# rgb-daughter.net
KiCad netlist of a schematic drawn in EAGLE
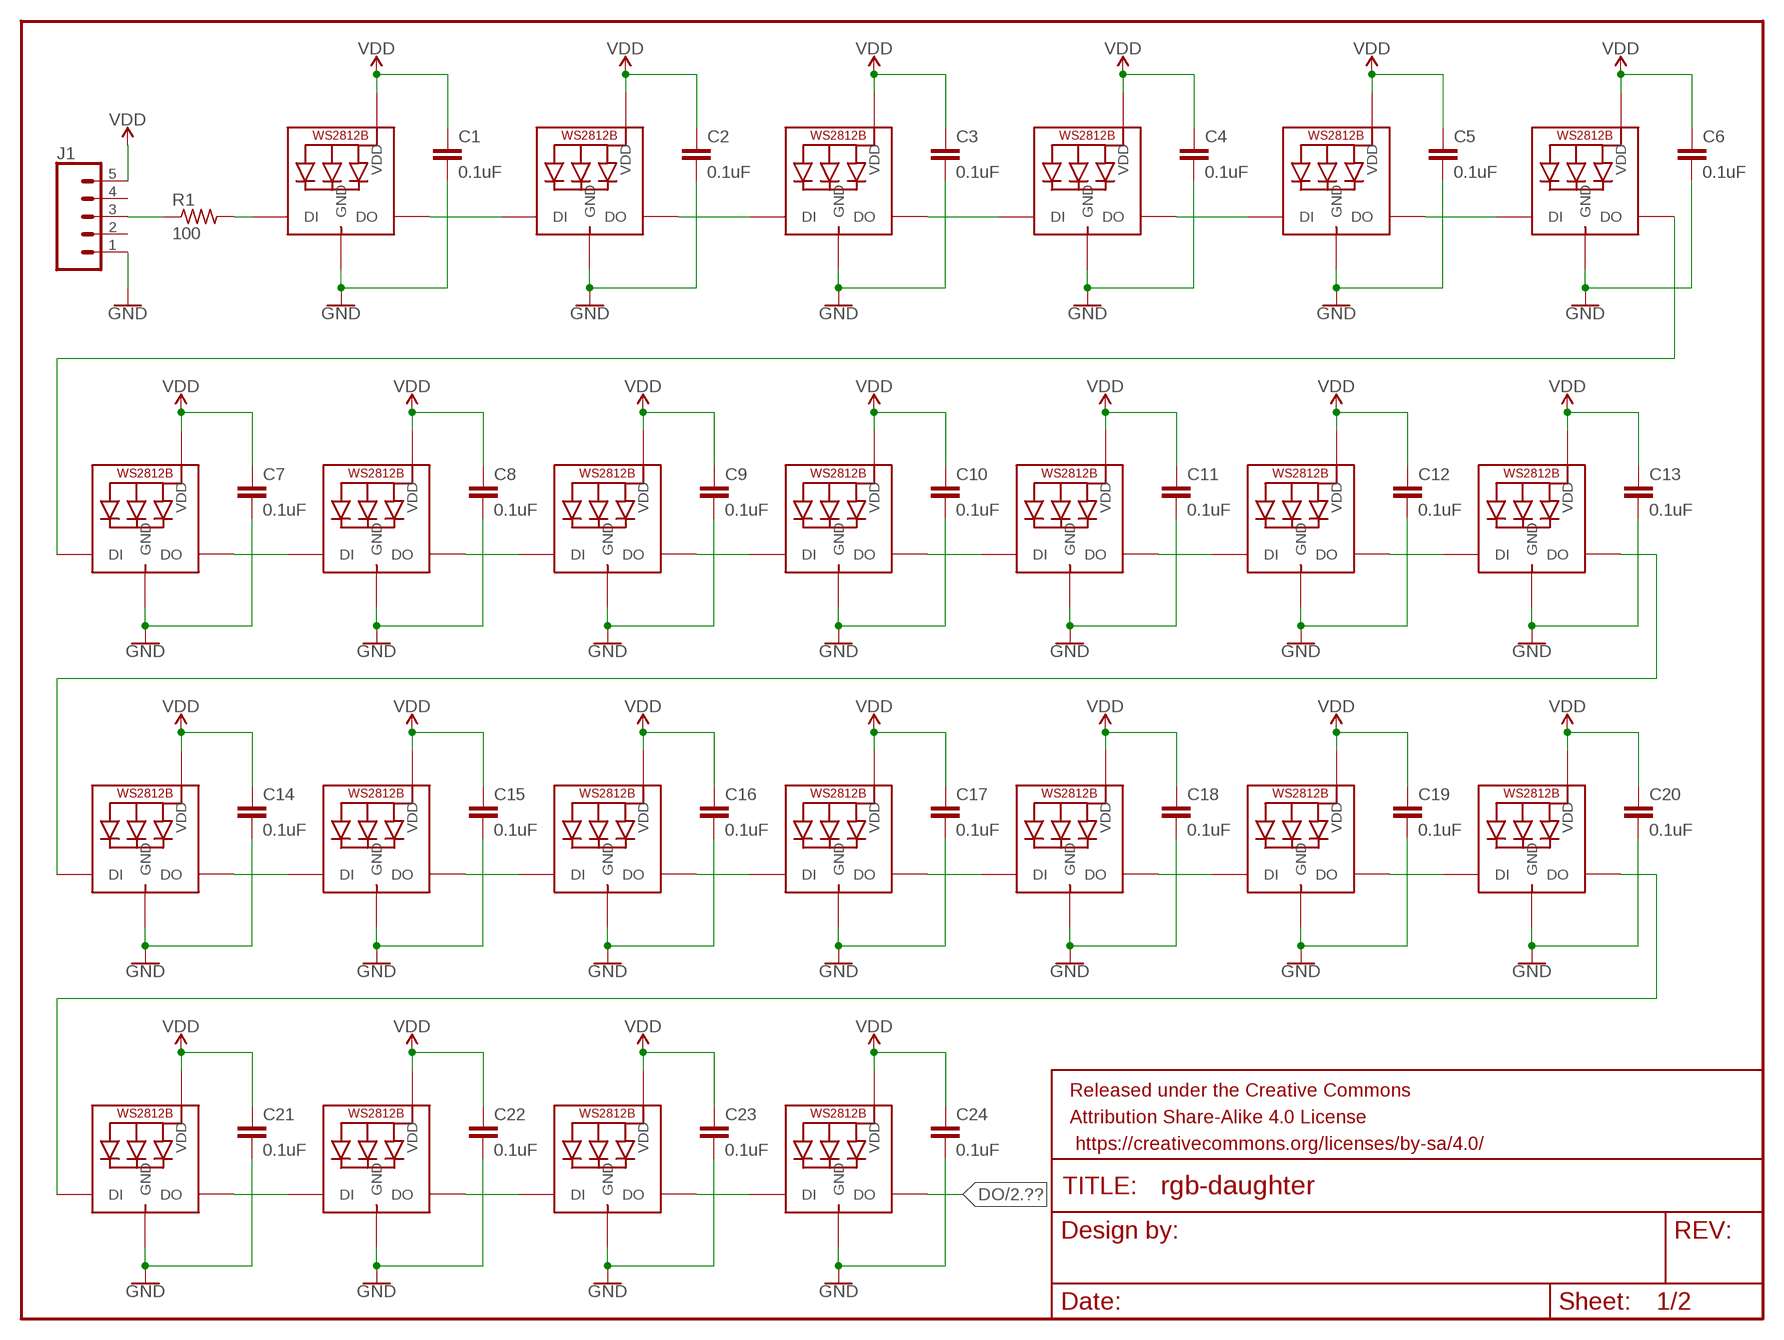
[diagram p0: schematic, sheet 1]
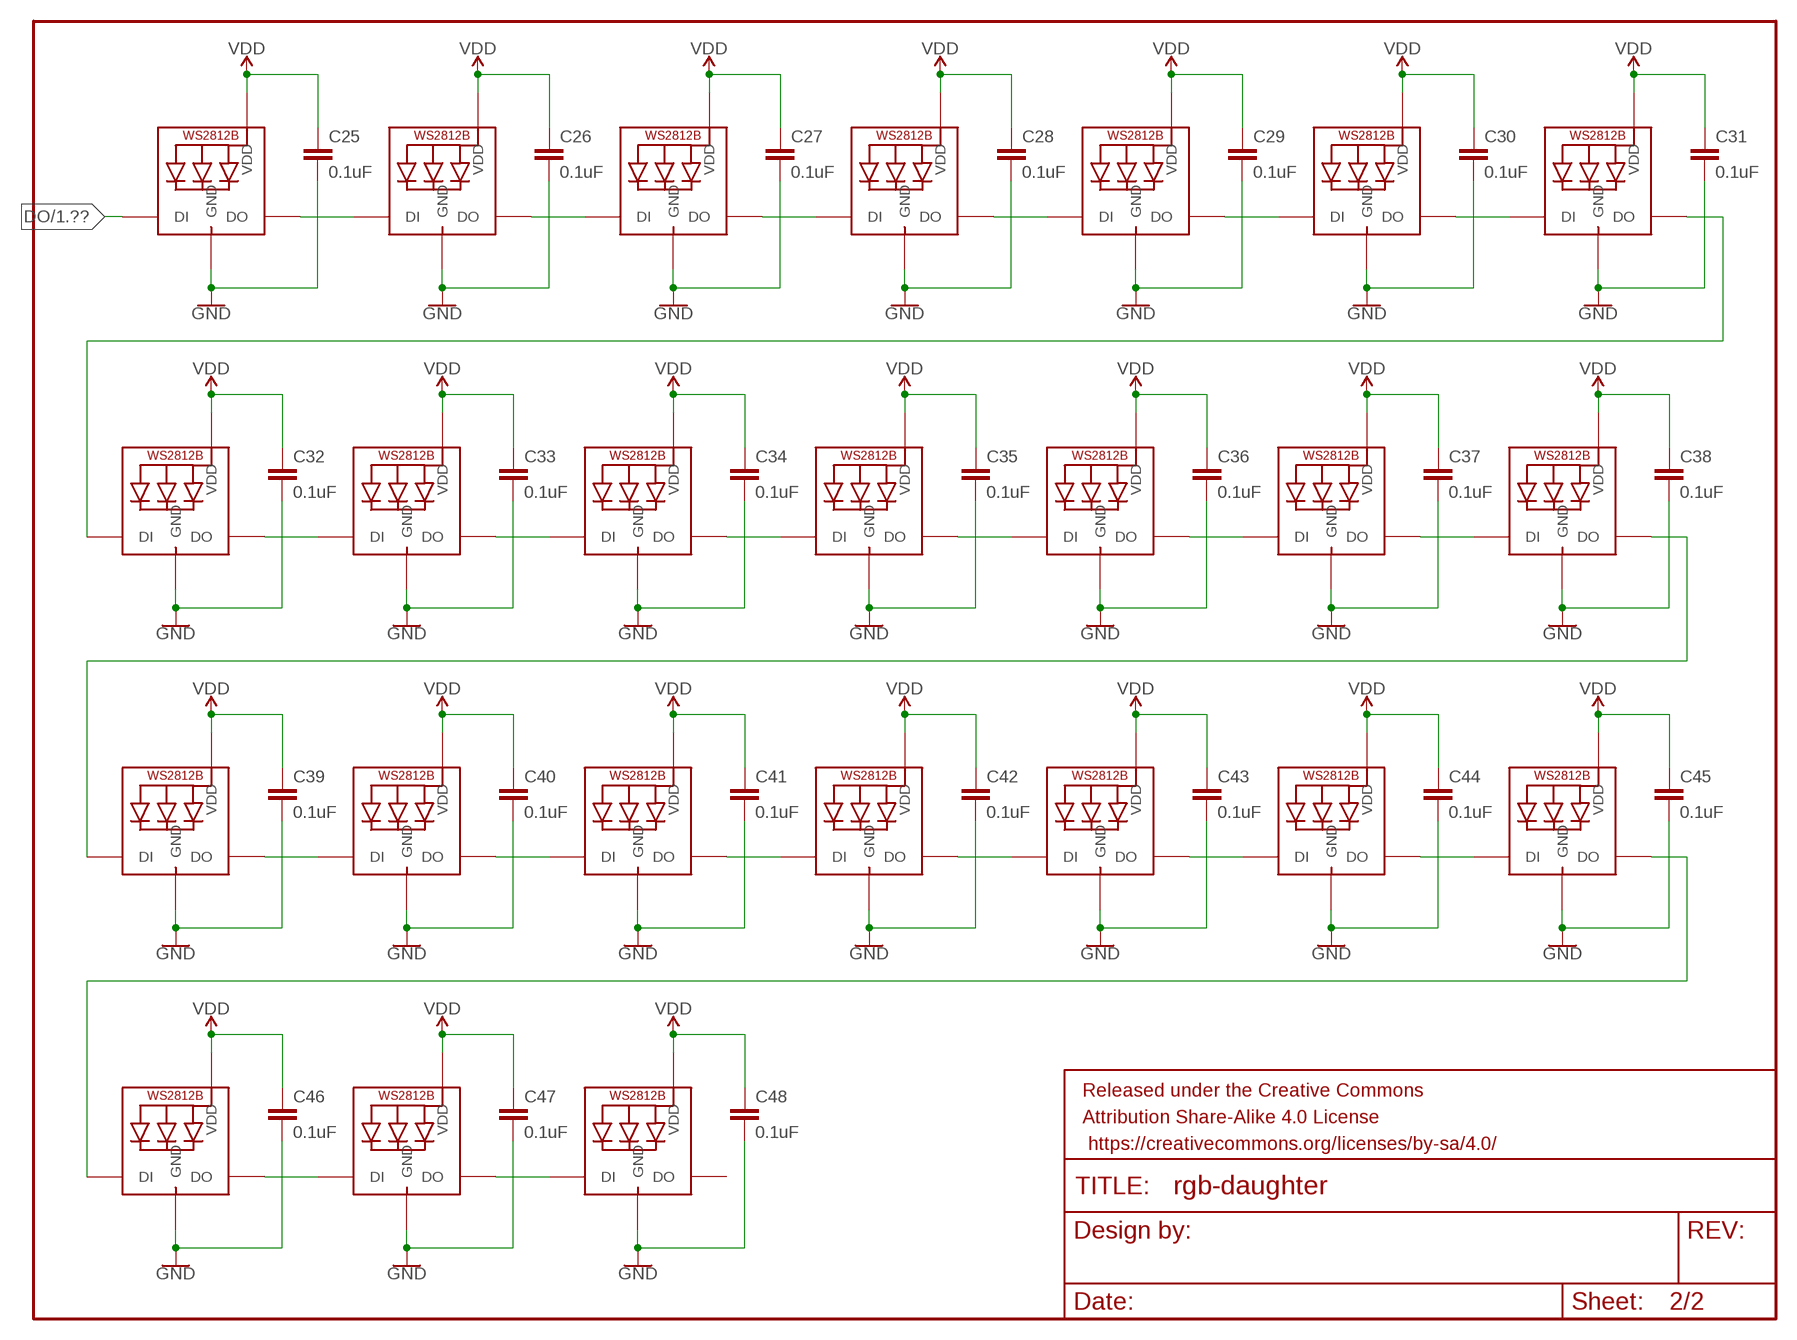
[diagram p1: schematic, sheet 2]

(export (version "E")
  (design (tool "Eeschema 10.0.6"))
  (components
    (comp (ref "C1")
      (value "0.1uF")
      (footprint "eagle-import:0603")
      (libsource (lib "eagle-import") (part "0.1UF-0603-25V-(+80/-20%)"))
    )
    (comp (ref "C2")
      (value "0.1uF")
      (footprint "eagle-import:0603")
      (libsource (lib "eagle-import") (part "0.1UF-0603-25V-(+80/-20%)"))
    )
    (comp (ref "C3")
      (value "0.1uF")
      (footprint "eagle-import:0603")
      (libsource (lib "eagle-import") (part "0.1UF-0603-25V-(+80/-20%)"))
    )
    (comp (ref "C4")
      (value "0.1uF")
      (footprint "eagle-import:0603")
      (libsource (lib "eagle-import") (part "0.1UF-0603-25V-(+80/-20%)"))
    )
    (comp (ref "C5")
      (value "0.1uF")
      (footprint "eagle-import:0603")
      (libsource (lib "eagle-import") (part "0.1UF-0603-25V-(+80/-20%)"))
    )
    (comp (ref "C6")
      (value "0.1uF")
      (footprint "eagle-import:0603")
      (libsource (lib "eagle-import") (part "0.1UF-0603-25V-(+80/-20%)"))
    )
    (comp (ref "C7")
      (value "0.1uF")
      (footprint "eagle-import:0603")
      (libsource (lib "eagle-import") (part "0.1UF-0603-25V-(+80/-20%)"))
    )
    (comp (ref "C8")
      (value "0.1uF")
      (footprint "eagle-import:0603")
      (libsource (lib "eagle-import") (part "0.1UF-0603-25V-(+80/-20%)"))
    )
    (comp (ref "C9")
      (value "0.1uF")
      (footprint "eagle-import:0603")
      (libsource (lib "eagle-import") (part "0.1UF-0603-25V-(+80/-20%)"))
    )
    (comp (ref "C10")
      (value "0.1uF")
      (footprint "eagle-import:0603")
      (libsource (lib "eagle-import") (part "0.1UF-0603-25V-(+80/-20%)"))
    )
    (comp (ref "C11")
      (value "0.1uF")
      (footprint "eagle-import:0603")
      (libsource (lib "eagle-import") (part "0.1UF-0603-25V-(+80/-20%)"))
    )
    (comp (ref "C12")
      (value "0.1uF")
      (footprint "eagle-import:0603")
      (libsource (lib "eagle-import") (part "0.1UF-0603-25V-(+80/-20%)"))
    )
    (comp (ref "C13")
      (value "0.1uF")
      (footprint "eagle-import:0603")
      (libsource (lib "eagle-import") (part "0.1UF-0603-25V-(+80/-20%)"))
    )
    (comp (ref "C14")
      (value "0.1uF")
      (footprint "eagle-import:0603")
      (libsource (lib "eagle-import") (part "0.1UF-0603-25V-(+80/-20%)"))
    )
    (comp (ref "C15")
      (value "0.1uF")
      (footprint "eagle-import:0603")
      (libsource (lib "eagle-import") (part "0.1UF-0603-25V-(+80/-20%)"))
    )
    (comp (ref "C16")
      (value "0.1uF")
      (footprint "eagle-import:0603")
      (libsource (lib "eagle-import") (part "0.1UF-0603-25V-(+80/-20%)"))
    )
    (comp (ref "C17")
      (value "0.1uF")
      (footprint "eagle-import:0603")
      (libsource (lib "eagle-import") (part "0.1UF-0603-25V-(+80/-20%)"))
    )
    (comp (ref "C18")
      (value "0.1uF")
      (footprint "eagle-import:0603")
      (libsource (lib "eagle-import") (part "0.1UF-0603-25V-(+80/-20%)"))
    )
    (comp (ref "C19")
      (value "0.1uF")
      (footprint "eagle-import:0603")
      (libsource (lib "eagle-import") (part "0.1UF-0603-25V-(+80/-20%)"))
    )
    (comp (ref "C20")
      (value "0.1uF")
      (footprint "eagle-import:0603")
      (libsource (lib "eagle-import") (part "0.1UF-0603-25V-(+80/-20%)"))
    )
    (comp (ref "C21")
      (value "0.1uF")
      (footprint "eagle-import:0603")
      (libsource (lib "eagle-import") (part "0.1UF-0603-25V-(+80/-20%)"))
    )
    (comp (ref "C22")
      (value "0.1uF")
      (footprint "eagle-import:0603")
      (libsource (lib "eagle-import") (part "0.1UF-0603-25V-(+80/-20%)"))
    )
    (comp (ref "C23")
      (value "0.1uF")
      (footprint "eagle-import:0603")
      (libsource (lib "eagle-import") (part "0.1UF-0603-25V-(+80/-20%)"))
    )
    (comp (ref "C24")
      (value "0.1uF")
      (footprint "eagle-import:0603")
      (libsource (lib "eagle-import") (part "0.1UF-0603-25V-(+80/-20%)"))
    )
    (comp (ref "FRAME1")
      (value "FRAME-LETTER")
      (footprint "eagle-import:CREATIVE_COMMONS")
      (libsource (lib "eagle-import") (part "FRAME-LETTER"))
    )
    (comp (ref "J1")
      (value "CONN_051.27MM")
      (footprint "eagle-import:1X05_1.27MM")
      (libsource (lib "eagle-import") (part "CONN_051.27MM"))
    )
    (comp (ref "LED1")
      (value "WS2812B3535")
      (footprint "eagle-import:LED3535")
      (libsource (lib "eagle-import") (part "WS2812B3535"))
    )
    (comp (ref "LED2")
      (value "WS2812B3535")
      (footprint "eagle-import:LED3535")
      (libsource (lib "eagle-import") (part "WS2812B3535"))
    )
    (comp (ref "LED3")
      (value "WS2812B3535")
      (footprint "eagle-import:LED3535")
      (libsource (lib "eagle-import") (part "WS2812B3535"))
    )
    (comp (ref "LED4")
      (value "WS2812B3535")
      (footprint "eagle-import:LED3535")
      (libsource (lib "eagle-import") (part "WS2812B3535"))
    )
    (comp (ref "LED5")
      (value "WS2812B3535")
      (footprint "eagle-import:LED3535")
      (libsource (lib "eagle-import") (part "WS2812B3535"))
    )
    (comp (ref "LED6")
      (value "WS2812B3535")
      (footprint "eagle-import:LED3535")
      (libsource (lib "eagle-import") (part "WS2812B3535"))
    )
    (comp (ref "LED7")
      (value "WS2812B3535")
      (footprint "eagle-import:LED3535")
      (libsource (lib "eagle-import") (part "WS2812B3535"))
    )
    (comp (ref "LED8")
      (value "WS2812B3535")
      (footprint "eagle-import:LED3535")
      (libsource (lib "eagle-import") (part "WS2812B3535"))
    )
    (comp (ref "LED9")
      (value "WS2812B3535")
      (footprint "eagle-import:LED3535")
      (libsource (lib "eagle-import") (part "WS2812B3535"))
    )
    (comp (ref "LED10")
      (value "WS2812B3535")
      (footprint "eagle-import:LED3535")
      (libsource (lib "eagle-import") (part "WS2812B3535"))
    )
    (comp (ref "LED11")
      (value "WS2812B3535")
      (footprint "eagle-import:LED3535")
      (libsource (lib "eagle-import") (part "WS2812B3535"))
    )
    (comp (ref "LED12")
      (value "WS2812B3535")
      (footprint "eagle-import:LED3535")
      (libsource (lib "eagle-import") (part "WS2812B3535"))
    )
    (comp (ref "LED13")
      (value "WS2812B3535")
      (footprint "eagle-import:LED3535")
      (libsource (lib "eagle-import") (part "WS2812B3535"))
    )
    (comp (ref "LED14")
      (value "WS2812B3535")
      (footprint "eagle-import:LED3535")
      (libsource (lib "eagle-import") (part "WS2812B3535"))
    )
    (comp (ref "LED15")
      (value "WS2812B3535")
      (footprint "eagle-import:LED3535")
      (libsource (lib "eagle-import") (part "WS2812B3535"))
    )
    (comp (ref "LED16")
      (value "WS2812B3535")
      (footprint "eagle-import:LED3535")
      (libsource (lib "eagle-import") (part "WS2812B3535"))
    )
    (comp (ref "LED17")
      (value "WS2812B3535")
      (footprint "eagle-import:LED3535")
      (libsource (lib "eagle-import") (part "WS2812B3535"))
    )
    (comp (ref "LED18")
      (value "WS2812B3535")
      (footprint "eagle-import:LED3535")
      (libsource (lib "eagle-import") (part "WS2812B3535"))
    )
    (comp (ref "LED19")
      (value "WS2812B3535")
      (footprint "eagle-import:LED3535")
      (libsource (lib "eagle-import") (part "WS2812B3535"))
    )
    (comp (ref "LED20")
      (value "WS2812B3535")
      (footprint "eagle-import:LED3535")
      (libsource (lib "eagle-import") (part "WS2812B3535"))
    )
    (comp (ref "LED21")
      (value "WS2812B3535")
      (footprint "eagle-import:LED3535")
      (libsource (lib "eagle-import") (part "WS2812B3535"))
    )
    (comp (ref "LED22")
      (value "WS2812B3535")
      (footprint "eagle-import:LED3535")
      (libsource (lib "eagle-import") (part "WS2812B3535"))
    )
    (comp (ref "LED23")
      (value "WS2812B3535")
      (footprint "eagle-import:LED3535")
      (libsource (lib "eagle-import") (part "WS2812B3535"))
    )
    (comp (ref "LED48")
      (value "WS2812B3535")
      (footprint "eagle-import:LED3535")
      (libsource (lib "eagle-import") (part "WS2812B3535"))
    )
    (comp (ref "R1")
      (value "100")
      (footprint "eagle-import:M0805")
      (libsource (lib "eagle-import") (part "R-US_M0805"))
    )
    (comp (ref "C25")
      (value "0.1uF")
      (footprint "eagle-import:0603")
      (libsource (lib "eagle-import") (part "0.1UF-0603-25V-(+80/-20%)"))
    )
    (comp (ref "C26")
      (value "0.1uF")
      (footprint "eagle-import:0603")
      (libsource (lib "eagle-import") (part "0.1UF-0603-25V-(+80/-20%)"))
    )
    (comp (ref "C27")
      (value "0.1uF")
      (footprint "eagle-import:0603")
      (libsource (lib "eagle-import") (part "0.1UF-0603-25V-(+80/-20%)"))
    )
    (comp (ref "C28")
      (value "0.1uF")
      (footprint "eagle-import:0603")
      (libsource (lib "eagle-import") (part "0.1UF-0603-25V-(+80/-20%)"))
    )
    (comp (ref "C29")
      (value "0.1uF")
      (footprint "eagle-import:0603")
      (libsource (lib "eagle-import") (part "0.1UF-0603-25V-(+80/-20%)"))
    )
    (comp (ref "C30")
      (value "0.1uF")
      (footprint "eagle-import:0603")
      (libsource (lib "eagle-import") (part "0.1UF-0603-25V-(+80/-20%)"))
    )
    (comp (ref "C31")
      (value "0.1uF")
      (footprint "eagle-import:0603")
      (libsource (lib "eagle-import") (part "0.1UF-0603-25V-(+80/-20%)"))
    )
    (comp (ref "C32")
      (value "0.1uF")
      (footprint "eagle-import:0603")
      (libsource (lib "eagle-import") (part "0.1UF-0603-25V-(+80/-20%)"))
    )
    (comp (ref "C33")
      (value "0.1uF")
      (footprint "eagle-import:0603")
      (libsource (lib "eagle-import") (part "0.1UF-0603-25V-(+80/-20%)"))
    )
    (comp (ref "C34")
      (value "0.1uF")
      (footprint "eagle-import:0603")
      (libsource (lib "eagle-import") (part "0.1UF-0603-25V-(+80/-20%)"))
    )
    (comp (ref "C35")
      (value "0.1uF")
      (footprint "eagle-import:0603")
      (libsource (lib "eagle-import") (part "0.1UF-0603-25V-(+80/-20%)"))
    )
    (comp (ref "C36")
      (value "0.1uF")
      (footprint "eagle-import:0603")
      (libsource (lib "eagle-import") (part "0.1UF-0603-25V-(+80/-20%)"))
    )
    (comp (ref "C37")
      (value "0.1uF")
      (footprint "eagle-import:0603")
      (libsource (lib "eagle-import") (part "0.1UF-0603-25V-(+80/-20%)"))
    )
    (comp (ref "C38")
      (value "0.1uF")
      (footprint "eagle-import:0603")
      (libsource (lib "eagle-import") (part "0.1UF-0603-25V-(+80/-20%)"))
    )
    (comp (ref "C39")
      (value "0.1uF")
      (footprint "eagle-import:0603")
      (libsource (lib "eagle-import") (part "0.1UF-0603-25V-(+80/-20%)"))
    )
    (comp (ref "C40")
      (value "0.1uF")
      (footprint "eagle-import:0603")
      (libsource (lib "eagle-import") (part "0.1UF-0603-25V-(+80/-20%)"))
    )
    (comp (ref "C41")
      (value "0.1uF")
      (footprint "eagle-import:0603")
      (libsource (lib "eagle-import") (part "0.1UF-0603-25V-(+80/-20%)"))
    )
    (comp (ref "C42")
      (value "0.1uF")
      (footprint "eagle-import:0603")
      (libsource (lib "eagle-import") (part "0.1UF-0603-25V-(+80/-20%)"))
    )
    (comp (ref "C43")
      (value "0.1uF")
      (footprint "eagle-import:0603")
      (libsource (lib "eagle-import") (part "0.1UF-0603-25V-(+80/-20%)"))
    )
    (comp (ref "C44")
      (value "0.1uF")
      (footprint "eagle-import:0603")
      (libsource (lib "eagle-import") (part "0.1UF-0603-25V-(+80/-20%)"))
    )
    (comp (ref "C45")
      (value "0.1uF")
      (footprint "eagle-import:0603")
      (libsource (lib "eagle-import") (part "0.1UF-0603-25V-(+80/-20%)"))
    )
    (comp (ref "C46")
      (value "0.1uF")
      (footprint "eagle-import:0603")
      (libsource (lib "eagle-import") (part "0.1UF-0603-25V-(+80/-20%)"))
    )
    (comp (ref "C47")
      (value "0.1uF")
      (footprint "eagle-import:0603")
      (libsource (lib "eagle-import") (part "0.1UF-0603-25V-(+80/-20%)"))
    )
    (comp (ref "C48")
      (value "0.1uF")
      (footprint "eagle-import:0603")
      (libsource (lib "eagle-import") (part "0.1UF-0603-25V-(+80/-20%)"))
    )
    (comp (ref "FRAME2")
      (value "FRAME-LETTER")
      (footprint "eagle-import:CREATIVE_COMMONS")
      (libsource (lib "eagle-import") (part "FRAME-LETTER"))
    )
    (comp (ref "LED24")
      (value "WS2812B3535")
      (footprint "eagle-import:LED3535")
      (libsource (lib "eagle-import") (part "WS2812B3535"))
    )
    (comp (ref "LED25")
      (value "WS2812B3535")
      (footprint "eagle-import:LED3535")
      (libsource (lib "eagle-import") (part "WS2812B3535"))
    )
    (comp (ref "LED26")
      (value "WS2812B3535")
      (footprint "eagle-import:LED3535")
      (libsource (lib "eagle-import") (part "WS2812B3535"))
    )
    (comp (ref "LED27")
      (value "WS2812B3535")
      (footprint "eagle-import:LED3535")
      (libsource (lib "eagle-import") (part "WS2812B3535"))
    )
    (comp (ref "LED28")
      (value "WS2812B3535")
      (footprint "eagle-import:LED3535")
      (libsource (lib "eagle-import") (part "WS2812B3535"))
    )
    (comp (ref "LED29")
      (value "WS2812B3535")
      (footprint "eagle-import:LED3535")
      (libsource (lib "eagle-import") (part "WS2812B3535"))
    )
    (comp (ref "LED30")
      (value "WS2812B3535")
      (footprint "eagle-import:LED3535")
      (libsource (lib "eagle-import") (part "WS2812B3535"))
    )
    (comp (ref "LED31")
      (value "WS2812B3535")
      (footprint "eagle-import:LED3535")
      (libsource (lib "eagle-import") (part "WS2812B3535"))
    )
    (comp (ref "LED32")
      (value "WS2812B3535")
      (footprint "eagle-import:LED3535")
      (libsource (lib "eagle-import") (part "WS2812B3535"))
    )
    (comp (ref "LED33")
      (value "WS2812B3535")
      (footprint "eagle-import:LED3535")
      (libsource (lib "eagle-import") (part "WS2812B3535"))
    )
    (comp (ref "LED34")
      (value "WS2812B3535")
      (footprint "eagle-import:LED3535")
      (libsource (lib "eagle-import") (part "WS2812B3535"))
    )
    (comp (ref "LED35")
      (value "WS2812B3535")
      (footprint "eagle-import:LED3535")
      (libsource (lib "eagle-import") (part "WS2812B3535"))
    )
    (comp (ref "LED36")
      (value "WS2812B3535")
      (footprint "eagle-import:LED3535")
      (libsource (lib "eagle-import") (part "WS2812B3535"))
    )
    (comp (ref "LED37")
      (value "WS2812B3535")
      (footprint "eagle-import:LED3535")
      (libsource (lib "eagle-import") (part "WS2812B3535"))
    )
    (comp (ref "LED38")
      (value "WS2812B3535")
      (footprint "eagle-import:LED3535")
      (libsource (lib "eagle-import") (part "WS2812B3535"))
    )
    (comp (ref "LED39")
      (value "WS2812B3535")
      (footprint "eagle-import:LED3535")
      (libsource (lib "eagle-import") (part "WS2812B3535"))
    )
    (comp (ref "LED40")
      (value "WS2812B3535")
      (footprint "eagle-import:LED3535")
      (libsource (lib "eagle-import") (part "WS2812B3535"))
    )
    (comp (ref "LED41")
      (value "WS2812B3535")
      (footprint "eagle-import:LED3535")
      (libsource (lib "eagle-import") (part "WS2812B3535"))
    )
    (comp (ref "LED42")
      (value "WS2812B3535")
      (footprint "eagle-import:LED3535")
      (libsource (lib "eagle-import") (part "WS2812B3535"))
    )
    (comp (ref "LED43")
      (value "WS2812B3535")
      (footprint "eagle-import:LED3535")
      (libsource (lib "eagle-import") (part "WS2812B3535"))
    )
    (comp (ref "LED44")
      (value "WS2812B3535")
      (footprint "eagle-import:LED3535")
      (libsource (lib "eagle-import") (part "WS2812B3535"))
    )
    (comp (ref "LED45")
      (value "WS2812B3535")
      (footprint "eagle-import:LED3535")
      (libsource (lib "eagle-import") (part "WS2812B3535"))
    )
    (comp (ref "LED46")
      (value "WS2812B3535")
      (footprint "eagle-import:LED3535")
      (libsource (lib "eagle-import") (part "WS2812B3535"))
    )
    (comp (ref "LED47")
      (value "WS2812B3535")
      (footprint "eagle-import:LED3535")
      (libsource (lib "eagle-import") (part "WS2812B3535"))
    )
  )
  (nets
    (net (code "1") (name "DO") (class "Default")
      (node (ref "LED24") (pin "1") (pinfunction "DI_1") (pintype "input"))
      (node (ref "LED48") (pin "3") (pinfunction "DO_3") (pintype "output"))
    )
    (net (code "2") (name "GND") (class "Default")
      (node (ref "C1") (pin "2") (pinfunction "2_2") (pintype "passive"))
      (node (ref "C10") (pin "2") (pinfunction "2_2") (pintype "passive"))
      (node (ref "C11") (pin "2") (pinfunction "2_2") (pintype "passive"))
      (node (ref "C12") (pin "2") (pinfunction "2_2") (pintype "passive"))
      (node (ref "C13") (pin "2") (pinfunction "2_2") (pintype "passive"))
      (node (ref "C14") (pin "2") (pinfunction "2_2") (pintype "passive"))
      (node (ref "C15") (pin "2") (pinfunction "2_2") (pintype "passive"))
      (node (ref "C16") (pin "2") (pinfunction "2_2") (pintype "passive"))
      (node (ref "C17") (pin "2") (pinfunction "2_2") (pintype "passive"))
      (node (ref "C18") (pin "2") (pinfunction "2_2") (pintype "passive"))
      (node (ref "C19") (pin "2") (pinfunction "2_2") (pintype "passive"))
      (node (ref "C2") (pin "2") (pinfunction "2_2") (pintype "passive"))
      (node (ref "C20") (pin "2") (pinfunction "2_2") (pintype "passive"))
      (node (ref "C21") (pin "2") (pinfunction "2_2") (pintype "passive"))
      (node (ref "C22") (pin "2") (pinfunction "2_2") (pintype "passive"))
      (node (ref "C23") (pin "2") (pinfunction "2_2") (pintype "passive"))
      (node (ref "C24") (pin "2") (pinfunction "2_2") (pintype "passive"))
      (node (ref "C25") (pin "2") (pinfunction "2_2") (pintype "passive"))
      (node (ref "C26") (pin "2") (pinfunction "2_2") (pintype "passive"))
      (node (ref "C27") (pin "2") (pinfunction "2_2") (pintype "passive"))
      (node (ref "C28") (pin "2") (pinfunction "2_2") (pintype "passive"))
      (node (ref "C29") (pin "2") (pinfunction "2_2") (pintype "passive"))
      (node (ref "C3") (pin "2") (pinfunction "2_2") (pintype "passive"))
      (node (ref "C30") (pin "2") (pinfunction "2_2") (pintype "passive"))
      (node (ref "C31") (pin "2") (pinfunction "2_2") (pintype "passive"))
      (node (ref "C32") (pin "2") (pinfunction "2_2") (pintype "passive"))
      (node (ref "C33") (pin "2") (pinfunction "2_2") (pintype "passive"))
      (node (ref "C34") (pin "2") (pinfunction "2_2") (pintype "passive"))
      (node (ref "C35") (pin "2") (pinfunction "2_2") (pintype "passive"))
      (node (ref "C36") (pin "2") (pinfunction "2_2") (pintype "passive"))
      (node (ref "C37") (pin "2") (pinfunction "2_2") (pintype "passive"))
      (node (ref "C38") (pin "2") (pinfunction "2_2") (pintype "passive"))
      (node (ref "C39") (pin "2") (pinfunction "2_2") (pintype "passive"))
      (node (ref "C4") (pin "2") (pinfunction "2_2") (pintype "passive"))
      (node (ref "C40") (pin "2") (pinfunction "2_2") (pintype "passive"))
      (node (ref "C41") (pin "2") (pinfunction "2_2") (pintype "passive"))
      (node (ref "C42") (pin "2") (pinfunction "2_2") (pintype "passive"))
      (node (ref "C43") (pin "2") (pinfunction "2_2") (pintype "passive"))
      (node (ref "C44") (pin "2") (pinfunction "2_2") (pintype "passive"))
      (node (ref "C45") (pin "2") (pinfunction "2_2") (pintype "passive"))
      (node (ref "C46") (pin "2") (pinfunction "2_2") (pintype "passive"))
      (node (ref "C47") (pin "2") (pinfunction "2_2") (pintype "passive"))
      (node (ref "C48") (pin "2") (pinfunction "2_2") (pintype "passive"))
      (node (ref "C5") (pin "2") (pinfunction "2_2") (pintype "passive"))
      (node (ref "C6") (pin "2") (pinfunction "2_2") (pintype "passive"))
      (node (ref "C7") (pin "2") (pinfunction "2_2") (pintype "passive"))
      (node (ref "C8") (pin "2") (pinfunction "2_2") (pintype "passive"))
      (node (ref "C9") (pin "2") (pinfunction "2_2") (pintype "passive"))
      (node (ref "J1") (pin "1") (pinfunction "1_1") (pintype "passive"))
      (node (ref "LED1") (pin "4") (pinfunction "GND_4") (pintype "power_in"))
      (node (ref "LED10") (pin "4") (pinfunction "GND_4") (pintype "power_in"))
      (node (ref "LED11") (pin "4") (pinfunction "GND_4") (pintype "power_in"))
      (node (ref "LED12") (pin "4") (pinfunction "GND_4") (pintype "power_in"))
      (node (ref "LED13") (pin "4") (pinfunction "GND_4") (pintype "power_in"))
      (node (ref "LED14") (pin "4") (pinfunction "GND_4") (pintype "power_in"))
      (node (ref "LED15") (pin "4") (pinfunction "GND_4") (pintype "power_in"))
      (node (ref "LED16") (pin "4") (pinfunction "GND_4") (pintype "power_in"))
      (node (ref "LED17") (pin "4") (pinfunction "GND_4") (pintype "power_in"))
      (node (ref "LED18") (pin "4") (pinfunction "GND_4") (pintype "power_in"))
      (node (ref "LED19") (pin "4") (pinfunction "GND_4") (pintype "power_in"))
      (node (ref "LED2") (pin "4") (pinfunction "GND_4") (pintype "power_in"))
      (node (ref "LED20") (pin "4") (pinfunction "GND_4") (pintype "power_in"))
      (node (ref "LED21") (pin "4") (pinfunction "GND_4") (pintype "power_in"))
      (node (ref "LED22") (pin "4") (pinfunction "GND_4") (pintype "power_in"))
      (node (ref "LED23") (pin "4") (pinfunction "GND_4") (pintype "power_in"))
      (node (ref "LED24") (pin "4") (pinfunction "GND_4") (pintype "power_in"))
      (node (ref "LED25") (pin "4") (pinfunction "GND_4") (pintype "power_in"))
      (node (ref "LED26") (pin "4") (pinfunction "GND_4") (pintype "power_in"))
      (node (ref "LED27") (pin "4") (pinfunction "GND_4") (pintype "power_in"))
      (node (ref "LED28") (pin "4") (pinfunction "GND_4") (pintype "power_in"))
      (node (ref "LED29") (pin "4") (pinfunction "GND_4") (pintype "power_in"))
      (node (ref "LED3") (pin "4") (pinfunction "GND_4") (pintype "power_in"))
      (node (ref "LED30") (pin "4") (pinfunction "GND_4") (pintype "power_in"))
      (node (ref "LED31") (pin "4") (pinfunction "GND_4") (pintype "power_in"))
      (node (ref "LED32") (pin "4") (pinfunction "GND_4") (pintype "power_in"))
      (node (ref "LED33") (pin "4") (pinfunction "GND_4") (pintype "power_in"))
      (node (ref "LED34") (pin "4") (pinfunction "GND_4") (pintype "power_in"))
      (node (ref "LED35") (pin "4") (pinfunction "GND_4") (pintype "power_in"))
      (node (ref "LED36") (pin "4") (pinfunction "GND_4") (pintype "power_in"))
      (node (ref "LED37") (pin "4") (pinfunction "GND_4") (pintype "power_in"))
      (node (ref "LED38") (pin "4") (pinfunction "GND_4") (pintype "power_in"))
      (node (ref "LED39") (pin "4") (pinfunction "GND_4") (pintype "power_in"))
      (node (ref "LED4") (pin "4") (pinfunction "GND_4") (pintype "power_in"))
      (node (ref "LED40") (pin "4") (pinfunction "GND_4") (pintype "power_in"))
      (node (ref "LED41") (pin "4") (pinfunction "GND_4") (pintype "power_in"))
      (node (ref "LED42") (pin "4") (pinfunction "GND_4") (pintype "power_in"))
      (node (ref "LED43") (pin "4") (pinfunction "GND_4") (pintype "power_in"))
      (node (ref "LED44") (pin "4") (pinfunction "GND_4") (pintype "power_in"))
      (node (ref "LED45") (pin "4") (pinfunction "GND_4") (pintype "power_in"))
      (node (ref "LED46") (pin "4") (pinfunction "GND_4") (pintype "power_in"))
      (node (ref "LED47") (pin "4") (pinfunction "GND_4") (pintype "power_in"))
      (node (ref "LED48") (pin "4") (pinfunction "GND_4") (pintype "power_in"))
      (node (ref "LED5") (pin "4") (pinfunction "GND_4") (pintype "power_in"))
      (node (ref "LED6") (pin "4") (pinfunction "GND_4") (pintype "power_in"))
      (node (ref "LED7") (pin "4") (pinfunction "GND_4") (pintype "power_in"))
      (node (ref "LED8") (pin "4") (pinfunction "GND_4") (pintype "power_in"))
      (node (ref "LED9") (pin "4") (pinfunction "GND_4") (pintype "power_in"))
    )
    (net (code "3") (name "Net-(J1-Pad3)") (class "Default")
      (node (ref "J1") (pin "3") (pinfunction "3_3") (pintype "passive"))
      (node (ref "R1") (pin "1") (pinfunction "1_1") (pintype "passive"))
    )
    (net (code "4") (name "Net-(LED1-DI)") (class "Default")
      (node (ref "LED1") (pin "1") (pinfunction "DI_1") (pintype "input"))
      (node (ref "R1") (pin "2") (pinfunction "2_2") (pintype "passive"))
    )
    (net (code "5") (name "Net-(LED1-DO)") (class "Default")
      (node (ref "LED1") (pin "3") (pinfunction "DO_3") (pintype "output"))
      (node (ref "LED2") (pin "1") (pinfunction "DI_1") (pintype "input"))
    )
    (net (code "6") (name "Net-(LED2-DO)") (class "Default")
      (node (ref "LED2") (pin "3") (pinfunction "DO_3") (pintype "output"))
      (node (ref "LED3") (pin "1") (pinfunction "DI_1") (pintype "input"))
    )
    (net (code "7") (name "Net-(LED3-DO)") (class "Default")
      (node (ref "LED3") (pin "3") (pinfunction "DO_3") (pintype "output"))
      (node (ref "LED4") (pin "1") (pinfunction "DI_1") (pintype "input"))
    )
    (net (code "8") (name "Net-(LED4-DO)") (class "Default")
      (node (ref "LED4") (pin "3") (pinfunction "DO_3") (pintype "output"))
      (node (ref "LED5") (pin "1") (pinfunction "DI_1") (pintype "input"))
    )
    (net (code "9") (name "Net-(LED5-DO)") (class "Default")
      (node (ref "LED5") (pin "3") (pinfunction "DO_3") (pintype "output"))
      (node (ref "LED6") (pin "1") (pinfunction "DI_1") (pintype "input"))
    )
    (net (code "10") (name "Net-(LED6-DO)") (class "Default")
      (node (ref "LED6") (pin "3") (pinfunction "DO_3") (pintype "output"))
      (node (ref "LED7") (pin "1") (pinfunction "DI_1") (pintype "input"))
    )
    (net (code "11") (name "Net-(LED7-DO)") (class "Default")
      (node (ref "LED7") (pin "3") (pinfunction "DO_3") (pintype "output"))
      (node (ref "LED8") (pin "1") (pinfunction "DI_1") (pintype "input"))
    )
    (net (code "12") (name "Net-(LED8-DO)") (class "Default")
      (node (ref "LED8") (pin "3") (pinfunction "DO_3") (pintype "output"))
      (node (ref "LED9") (pin "1") (pinfunction "DI_1") (pintype "input"))
    )
    (net (code "13") (name "Net-(LED10-DI)") (class "Default")
      (node (ref "LED10") (pin "1") (pinfunction "DI_1") (pintype "input"))
      (node (ref "LED9") (pin "3") (pinfunction "DO_3") (pintype "output"))
    )
    (net (code "14") (name "Net-(LED10-DO)") (class "Default")
      (node (ref "LED10") (pin "3") (pinfunction "DO_3") (pintype "output"))
      (node (ref "LED11") (pin "1") (pinfunction "DI_1") (pintype "input"))
    )
    (net (code "15") (name "Net-(LED11-DO)") (class "Default")
      (node (ref "LED11") (pin "3") (pinfunction "DO_3") (pintype "output"))
      (node (ref "LED12") (pin "1") (pinfunction "DI_1") (pintype "input"))
    )
    (net (code "16") (name "Net-(LED12-DO)") (class "Default")
      (node (ref "LED12") (pin "3") (pinfunction "DO_3") (pintype "output"))
      (node (ref "LED13") (pin "1") (pinfunction "DI_1") (pintype "input"))
    )
    (net (code "17") (name "Net-(LED13-DO)") (class "Default")
      (node (ref "LED13") (pin "3") (pinfunction "DO_3") (pintype "output"))
      (node (ref "LED14") (pin "1") (pinfunction "DI_1") (pintype "input"))
    )
    (net (code "18") (name "Net-(LED14-DO)") (class "Default")
      (node (ref "LED14") (pin "3") (pinfunction "DO_3") (pintype "output"))
      (node (ref "LED15") (pin "1") (pinfunction "DI_1") (pintype "input"))
    )
    (net (code "19") (name "Net-(LED15-DO)") (class "Default")
      (node (ref "LED15") (pin "3") (pinfunction "DO_3") (pintype "output"))
      (node (ref "LED16") (pin "1") (pinfunction "DI_1") (pintype "input"))
    )
    (net (code "20") (name "Net-(LED16-DO)") (class "Default")
      (node (ref "LED16") (pin "3") (pinfunction "DO_3") (pintype "output"))
      (node (ref "LED17") (pin "1") (pinfunction "DI_1") (pintype "input"))
    )
    (net (code "21") (name "Net-(LED17-DO)") (class "Default")
      (node (ref "LED17") (pin "3") (pinfunction "DO_3") (pintype "output"))
      (node (ref "LED18") (pin "1") (pinfunction "DI_1") (pintype "input"))
    )
    (net (code "22") (name "Net-(LED18-DO)") (class "Default")
      (node (ref "LED18") (pin "3") (pinfunction "DO_3") (pintype "output"))
      (node (ref "LED19") (pin "1") (pinfunction "DI_1") (pintype "input"))
    )
    (net (code "23") (name "Net-(LED19-DO)") (class "Default")
      (node (ref "LED19") (pin "3") (pinfunction "DO_3") (pintype "output"))
      (node (ref "LED20") (pin "1") (pinfunction "DI_1") (pintype "input"))
    )
    (net (code "24") (name "Net-(LED20-DO)") (class "Default")
      (node (ref "LED20") (pin "3") (pinfunction "DO_3") (pintype "output"))
      (node (ref "LED21") (pin "1") (pinfunction "DI_1") (pintype "input"))
    )
    (net (code "25") (name "Net-(LED21-DO)") (class "Default")
      (node (ref "LED21") (pin "3") (pinfunction "DO_3") (pintype "output"))
      (node (ref "LED22") (pin "1") (pinfunction "DI_1") (pintype "input"))
    )
    (net (code "26") (name "Net-(LED22-DO)") (class "Default")
      (node (ref "LED22") (pin "3") (pinfunction "DO_3") (pintype "output"))
      (node (ref "LED23") (pin "1") (pinfunction "DI_1") (pintype "input"))
    )
    (net (code "27") (name "Net-(LED23-DO)") (class "Default")
      (node (ref "LED23") (pin "3") (pinfunction "DO_3") (pintype "output"))
      (node (ref "LED48") (pin "1") (pinfunction "DI_1") (pintype "input"))
    )
    (net (code "28") (name "Net-(LED24-DO)") (class "Default")
      (node (ref "LED24") (pin "3") (pinfunction "DO_3") (pintype "output"))
      (node (ref "LED25") (pin "1") (pinfunction "DI_1") (pintype "input"))
    )
    (net (code "29") (name "Net-(LED25-DO)") (class "Default")
      (node (ref "LED25") (pin "3") (pinfunction "DO_3") (pintype "output"))
      (node (ref "LED26") (pin "1") (pinfunction "DI_1") (pintype "input"))
    )
    (net (code "30") (name "Net-(LED26-DO)") (class "Default")
      (node (ref "LED26") (pin "3") (pinfunction "DO_3") (pintype "output"))
      (node (ref "LED27") (pin "1") (pinfunction "DI_1") (pintype "input"))
    )
    (net (code "31") (name "Net-(LED27-DO)") (class "Default")
      (node (ref "LED27") (pin "3") (pinfunction "DO_3") (pintype "output"))
      (node (ref "LED28") (pin "1") (pinfunction "DI_1") (pintype "input"))
    )
    (net (code "32") (name "Net-(LED28-DO)") (class "Default")
      (node (ref "LED28") (pin "3") (pinfunction "DO_3") (pintype "output"))
      (node (ref "LED29") (pin "1") (pinfunction "DI_1") (pintype "input"))
    )
    (net (code "33") (name "Net-(LED29-DO)") (class "Default")
      (node (ref "LED29") (pin "3") (pinfunction "DO_3") (pintype "output"))
      (node (ref "LED30") (pin "1") (pinfunction "DI_1") (pintype "input"))
    )
    (net (code "34") (name "Net-(LED30-DO)") (class "Default")
      (node (ref "LED30") (pin "3") (pinfunction "DO_3") (pintype "output"))
      (node (ref "LED31") (pin "1") (pinfunction "DI_1") (pintype "input"))
    )
    (net (code "35") (name "Net-(LED31-DO)") (class "Default")
      (node (ref "LED31") (pin "3") (pinfunction "DO_3") (pintype "output"))
      (node (ref "LED32") (pin "1") (pinfunction "DI_1") (pintype "input"))
    )
    (net (code "36") (name "Net-(LED32-DO)") (class "Default")
      (node (ref "LED32") (pin "3") (pinfunction "DO_3") (pintype "output"))
      (node (ref "LED33") (pin "1") (pinfunction "DI_1") (pintype "input"))
    )
    (net (code "37") (name "Net-(LED33-DO)") (class "Default")
      (node (ref "LED33") (pin "3") (pinfunction "DO_3") (pintype "output"))
      (node (ref "LED34") (pin "1") (pinfunction "DI_1") (pintype "input"))
    )
    (net (code "38") (name "Net-(LED34-DO)") (class "Default")
      (node (ref "LED34") (pin "3") (pinfunction "DO_3") (pintype "output"))
      (node (ref "LED35") (pin "1") (pinfunction "DI_1") (pintype "input"))
    )
    (net (code "39") (name "Net-(LED35-DO)") (class "Default")
      (node (ref "LED35") (pin "3") (pinfunction "DO_3") (pintype "output"))
      (node (ref "LED36") (pin "1") (pinfunction "DI_1") (pintype "input"))
    )
    (net (code "40") (name "Net-(LED36-DO)") (class "Default")
      (node (ref "LED36") (pin "3") (pinfunction "DO_3") (pintype "output"))
      (node (ref "LED37") (pin "1") (pinfunction "DI_1") (pintype "input"))
    )
    (net (code "41") (name "Net-(LED37-DO)") (class "Default")
      (node (ref "LED37") (pin "3") (pinfunction "DO_3") (pintype "output"))
      (node (ref "LED38") (pin "1") (pinfunction "DI_1") (pintype "input"))
    )
    (net (code "42") (name "Net-(LED38-DO)") (class "Default")
      (node (ref "LED38") (pin "3") (pinfunction "DO_3") (pintype "output"))
      (node (ref "LED39") (pin "1") (pinfunction "DI_1") (pintype "input"))
    )
    (net (code "43") (name "Net-(LED39-DO)") (class "Default")
      (node (ref "LED39") (pin "3") (pinfunction "DO_3") (pintype "output"))
      (node (ref "LED40") (pin "1") (pinfunction "DI_1") (pintype "input"))
    )
    (net (code "44") (name "Net-(LED40-DO)") (class "Default")
      (node (ref "LED40") (pin "3") (pinfunction "DO_3") (pintype "output"))
      (node (ref "LED41") (pin "1") (pinfunction "DI_1") (pintype "input"))
    )
    (net (code "45") (name "Net-(LED41-DO)") (class "Default")
      (node (ref "LED41") (pin "3") (pinfunction "DO_3") (pintype "output"))
      (node (ref "LED42") (pin "1") (pinfunction "DI_1") (pintype "input"))
    )
    (net (code "46") (name "Net-(LED42-DO)") (class "Default")
      (node (ref "LED42") (pin "3") (pinfunction "DO_3") (pintype "output"))
      (node (ref "LED43") (pin "1") (pinfunction "DI_1") (pintype "input"))
    )
    (net (code "47") (name "Net-(LED43-DO)") (class "Default")
      (node (ref "LED43") (pin "3") (pinfunction "DO_3") (pintype "output"))
      (node (ref "LED44") (pin "1") (pinfunction "DI_1") (pintype "input"))
    )
    (net (code "48") (name "Net-(LED44-DO)") (class "Default")
      (node (ref "LED44") (pin "3") (pinfunction "DO_3") (pintype "output"))
      (node (ref "LED45") (pin "1") (pinfunction "DI_1") (pintype "input"))
    )
    (net (code "49") (name "Net-(LED45-DO)") (class "Default")
      (node (ref "LED45") (pin "3") (pinfunction "DO_3") (pintype "output"))
      (node (ref "LED46") (pin "1") (pinfunction "DI_1") (pintype "input"))
    )
    (net (code "50") (name "Net-(LED46-DO)") (class "Default")
      (node (ref "LED46") (pin "3") (pinfunction "DO_3") (pintype "output"))
      (node (ref "LED47") (pin "1") (pinfunction "DI_1") (pintype "input"))
    )
    (net (code "51") (name "VDD") (class "Default")
      (node (ref "C1") (pin "1") (pinfunction "1_1") (pintype "passive"))
      (node (ref "C10") (pin "1") (pinfunction "1_1") (pintype "passive"))
      (node (ref "C11") (pin "1") (pinfunction "1_1") (pintype "passive"))
      (node (ref "C12") (pin "1") (pinfunction "1_1") (pintype "passive"))
      (node (ref "C13") (pin "1") (pinfunction "1_1") (pintype "passive"))
      (node (ref "C14") (pin "1") (pinfunction "1_1") (pintype "passive"))
      (node (ref "C15") (pin "1") (pinfunction "1_1") (pintype "passive"))
      (node (ref "C16") (pin "1") (pinfunction "1_1") (pintype "passive"))
      (node (ref "C17") (pin "1") (pinfunction "1_1") (pintype "passive"))
      (node (ref "C18") (pin "1") (pinfunction "1_1") (pintype "passive"))
      (node (ref "C19") (pin "1") (pinfunction "1_1") (pintype "passive"))
      (node (ref "C2") (pin "1") (pinfunction "1_1") (pintype "passive"))
      (node (ref "C20") (pin "1") (pinfunction "1_1") (pintype "passive"))
      (node (ref "C21") (pin "1") (pinfunction "1_1") (pintype "passive"))
      (node (ref "C22") (pin "1") (pinfunction "1_1") (pintype "passive"))
      (node (ref "C23") (pin "1") (pinfunction "1_1") (pintype "passive"))
      (node (ref "C24") (pin "1") (pinfunction "1_1") (pintype "passive"))
      (node (ref "C25") (pin "1") (pinfunction "1_1") (pintype "passive"))
      (node (ref "C26") (pin "1") (pinfunction "1_1") (pintype "passive"))
      (node (ref "C27") (pin "1") (pinfunction "1_1") (pintype "passive"))
      (node (ref "C28") (pin "1") (pinfunction "1_1") (pintype "passive"))
      (node (ref "C29") (pin "1") (pinfunction "1_1") (pintype "passive"))
      (node (ref "C3") (pin "1") (pinfunction "1_1") (pintype "passive"))
      (node (ref "C30") (pin "1") (pinfunction "1_1") (pintype "passive"))
      (node (ref "C31") (pin "1") (pinfunction "1_1") (pintype "passive"))
      (node (ref "C32") (pin "1") (pinfunction "1_1") (pintype "passive"))
      (node (ref "C33") (pin "1") (pinfunction "1_1") (pintype "passive"))
      (node (ref "C34") (pin "1") (pinfunction "1_1") (pintype "passive"))
      (node (ref "C35") (pin "1") (pinfunction "1_1") (pintype "passive"))
      (node (ref "C36") (pin "1") (pinfunction "1_1") (pintype "passive"))
      (node (ref "C37") (pin "1") (pinfunction "1_1") (pintype "passive"))
      (node (ref "C38") (pin "1") (pinfunction "1_1") (pintype "passive"))
      (node (ref "C39") (pin "1") (pinfunction "1_1") (pintype "passive"))
      (node (ref "C4") (pin "1") (pinfunction "1_1") (pintype "passive"))
      (node (ref "C40") (pin "1") (pinfunction "1_1") (pintype "passive"))
      (node (ref "C41") (pin "1") (pinfunction "1_1") (pintype "passive"))
      (node (ref "C42") (pin "1") (pinfunction "1_1") (pintype "passive"))
      (node (ref "C43") (pin "1") (pinfunction "1_1") (pintype "passive"))
      (node (ref "C44") (pin "1") (pinfunction "1_1") (pintype "passive"))
      (node (ref "C45") (pin "1") (pinfunction "1_1") (pintype "passive"))
      (node (ref "C46") (pin "1") (pinfunction "1_1") (pintype "passive"))
      (node (ref "C47") (pin "1") (pinfunction "1_1") (pintype "passive"))
      (node (ref "C48") (pin "1") (pinfunction "1_1") (pintype "passive"))
      (node (ref "C5") (pin "1") (pinfunction "1_1") (pintype "passive"))
      (node (ref "C6") (pin "1") (pinfunction "1_1") (pintype "passive"))
      (node (ref "C7") (pin "1") (pinfunction "1_1") (pintype "passive"))
      (node (ref "C8") (pin "1") (pinfunction "1_1") (pintype "passive"))
      (node (ref "C9") (pin "1") (pinfunction "1_1") (pintype "passive"))
      (node (ref "J1") (pin "5") (pinfunction "5_5") (pintype "passive"))
      (node (ref "LED1") (pin "2") (pinfunction "VDD_2") (pintype "power_in"))
      (node (ref "LED10") (pin "2") (pinfunction "VDD_2") (pintype "power_in"))
      (node (ref "LED11") (pin "2") (pinfunction "VDD_2") (pintype "power_in"))
      (node (ref "LED12") (pin "2") (pinfunction "VDD_2") (pintype "power_in"))
      (node (ref "LED13") (pin "2") (pinfunction "VDD_2") (pintype "power_in"))
      (node (ref "LED14") (pin "2") (pinfunction "VDD_2") (pintype "power_in"))
      (node (ref "LED15") (pin "2") (pinfunction "VDD_2") (pintype "power_in"))
      (node (ref "LED16") (pin "2") (pinfunction "VDD_2") (pintype "power_in"))
      (node (ref "LED17") (pin "2") (pinfunction "VDD_2") (pintype "power_in"))
      (node (ref "LED18") (pin "2") (pinfunction "VDD_2") (pintype "power_in"))
      (node (ref "LED19") (pin "2") (pinfunction "VDD_2") (pintype "power_in"))
      (node (ref "LED2") (pin "2") (pinfunction "VDD_2") (pintype "power_in"))
      (node (ref "LED20") (pin "2") (pinfunction "VDD_2") (pintype "power_in"))
      (node (ref "LED21") (pin "2") (pinfunction "VDD_2") (pintype "power_in"))
      (node (ref "LED22") (pin "2") (pinfunction "VDD_2") (pintype "power_in"))
      (node (ref "LED23") (pin "2") (pinfunction "VDD_2") (pintype "power_in"))
      (node (ref "LED24") (pin "2") (pinfunction "VDD_2") (pintype "power_in"))
      (node (ref "LED25") (pin "2") (pinfunction "VDD_2") (pintype "power_in"))
      (node (ref "LED26") (pin "2") (pinfunction "VDD_2") (pintype "power_in"))
      (node (ref "LED27") (pin "2") (pinfunction "VDD_2") (pintype "power_in"))
      (node (ref "LED28") (pin "2") (pinfunction "VDD_2") (pintype "power_in"))
      (node (ref "LED29") (pin "2") (pinfunction "VDD_2") (pintype "power_in"))
      (node (ref "LED3") (pin "2") (pinfunction "VDD_2") (pintype "power_in"))
      (node (ref "LED30") (pin "2") (pinfunction "VDD_2") (pintype "power_in"))
      (node (ref "LED31") (pin "2") (pinfunction "VDD_2") (pintype "power_in"))
      (node (ref "LED32") (pin "2") (pinfunction "VDD_2") (pintype "power_in"))
      (node (ref "LED33") (pin "2") (pinfunction "VDD_2") (pintype "power_in"))
      (node (ref "LED34") (pin "2") (pinfunction "VDD_2") (pintype "power_in"))
      (node (ref "LED35") (pin "2") (pinfunction "VDD_2") (pintype "power_in"))
      (node (ref "LED36") (pin "2") (pinfunction "VDD_2") (pintype "power_in"))
      (node (ref "LED37") (pin "2") (pinfunction "VDD_2") (pintype "power_in"))
      (node (ref "LED38") (pin "2") (pinfunction "VDD_2") (pintype "power_in"))
      (node (ref "LED39") (pin "2") (pinfunction "VDD_2") (pintype "power_in"))
      (node (ref "LED4") (pin "2") (pinfunction "VDD_2") (pintype "power_in"))
      (node (ref "LED40") (pin "2") (pinfunction "VDD_2") (pintype "power_in"))
      (node (ref "LED41") (pin "2") (pinfunction "VDD_2") (pintype "power_in"))
      (node (ref "LED42") (pin "2") (pinfunction "VDD_2") (pintype "power_in"))
      (node (ref "LED43") (pin "2") (pinfunction "VDD_2") (pintype "power_in"))
      (node (ref "LED44") (pin "2") (pinfunction "VDD_2") (pintype "power_in"))
      (node (ref "LED45") (pin "2") (pinfunction "VDD_2") (pintype "power_in"))
      (node (ref "LED46") (pin "2") (pinfunction "VDD_2") (pintype "power_in"))
      (node (ref "LED47") (pin "2") (pinfunction "VDD_2") (pintype "power_in"))
      (node (ref "LED48") (pin "2") (pinfunction "VDD_2") (pintype "power_in"))
      (node (ref "LED5") (pin "2") (pinfunction "VDD_2") (pintype "power_in"))
      (node (ref "LED6") (pin "2") (pinfunction "VDD_2") (pintype "power_in"))
      (node (ref "LED7") (pin "2") (pinfunction "VDD_2") (pintype "power_in"))
      (node (ref "LED8") (pin "2") (pinfunction "VDD_2") (pintype "power_in"))
      (node (ref "LED9") (pin "2") (pinfunction "VDD_2") (pintype "power_in"))
    )
    (net (code "52") (name "unconnected-(J1-Pad2)") (class "Default")
      (node (ref "J1") (pin "2") (pinfunction "2_2") (pintype "passive"))
    )
    (net (code "53") (name "unconnected-(J1-Pad4)") (class "Default")
      (node (ref "J1") (pin "4") (pinfunction "4_4") (pintype "passive"))
    )
    (net (code "54") (name "unconnected-(LED47-DO-Pad3)") (class "Default")
      (node (ref "LED47") (pin "3") (pinfunction "DO_3") (pintype "output"))
    )
  )
)
